# TheSmartTenDollarJob.net
KiCad netlist of a schematic drawn in EAGLE
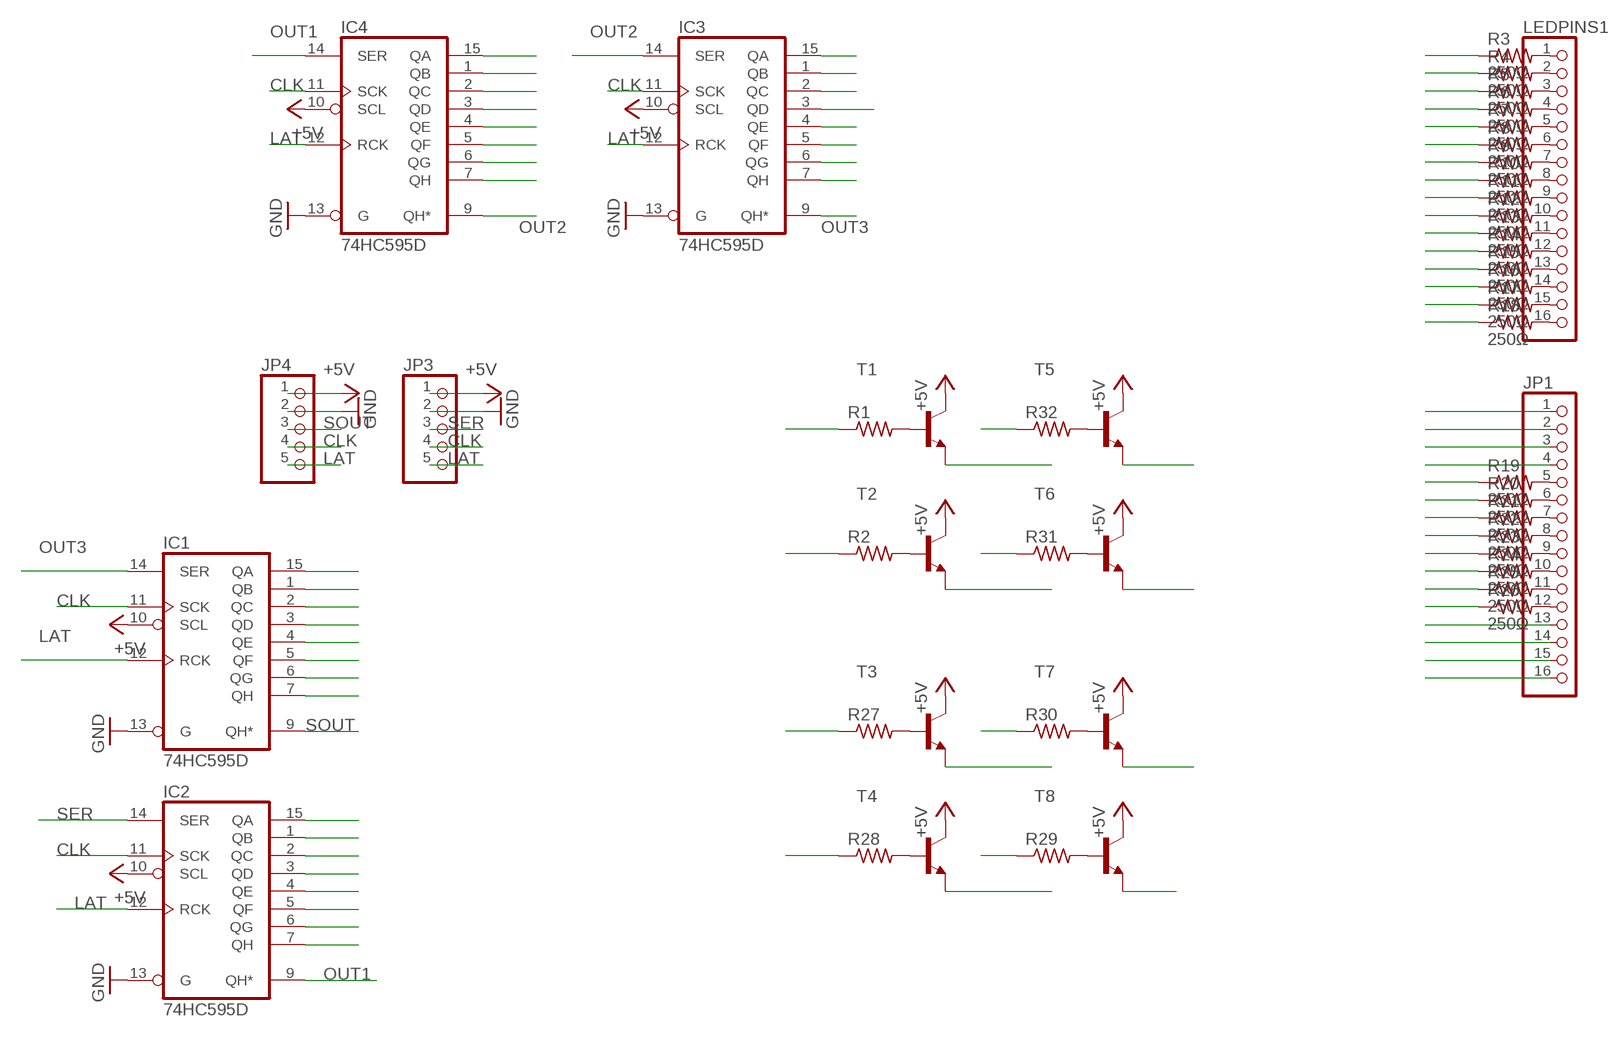
[diagram p0: schematic, sheet 1]

(export (version "E")
  (design (tool "Eeschema 10.0.6"))
  (components
    (comp (ref "IC1")
      (value "74HC595D")
      (footprint "eagle-import:SO16")
      (libsource (lib "eagle-import") (part "74595DHC"))
    )
    (comp (ref "IC2")
      (value "74HC595D")
      (footprint "eagle-import:SO16")
      (libsource (lib "eagle-import") (part "74595DHC"))
    )
    (comp (ref "IC3")
      (value "74HC595D")
      (footprint "eagle-import:SO16")
      (libsource (lib "eagle-import") (part "74595DHC"))
    )
    (comp (ref "IC4")
      (value "74HC595D")
      (footprint "eagle-import:SO16")
      (libsource (lib "eagle-import") (part "74595DHC"))
    )
    (comp (ref "JP1")
      (value "PINHD-1X16")
      (footprint "eagle-import:1X16")
      (libsource (lib "eagle-import") (part "PINHD-1X16"))
    )
    (comp (ref "JP3")
      (value "PINHD-1X5")
      (footprint "eagle-import:1X05")
      (libsource (lib "eagle-import") (part "PINHD-1X5"))
    )
    (comp (ref "JP4")
      (value "PINHD-1X5")
      (footprint "eagle-import:1X05")
      (libsource (lib "eagle-import") (part "PINHD-1X5"))
    )
    (comp (ref "LEDPINS1")
      (value "PINHD-1X16")
      (footprint "eagle-import:1X16")
      (libsource (lib "eagle-import") (part "PINHD-1X16"))
    )
    (comp (ref "R1")
      (value "R-US_R0603")
      (footprint "eagle-import:R0603")
      (libsource (lib "eagle-import") (part "resistor_R-US_R0603"))
    )
    (comp (ref "R2")
      (value "R-US_R0603")
      (footprint "eagle-import:R0603")
      (libsource (lib "eagle-import") (part "resistor_R-US_R0603"))
    )
    (comp (ref "R3")
      (value "250Ω")
      (footprint "eagle-import:R0603")
      (libsource (lib "eagle-import") (part "R-US_R0603"))
    )
    (comp (ref "R4")
      (value "250Ω")
      (footprint "eagle-import:R0603")
      (libsource (lib "eagle-import") (part "R-US_R0603"))
    )
    (comp (ref "R5")
      (value "250Ω")
      (footprint "eagle-import:R0603")
      (libsource (lib "eagle-import") (part "R-US_R0603"))
    )
    (comp (ref "R6")
      (value "250Ω")
      (footprint "eagle-import:R0603")
      (libsource (lib "eagle-import") (part "R-US_R0603"))
    )
    (comp (ref "R7")
      (value "250Ω")
      (footprint "eagle-import:R0603")
      (libsource (lib "eagle-import") (part "R-US_R0603"))
    )
    (comp (ref "R8")
      (value "250Ω")
      (footprint "eagle-import:R0603")
      (libsource (lib "eagle-import") (part "R-US_R0603"))
    )
    (comp (ref "R9")
      (value "250Ω")
      (footprint "eagle-import:R0603")
      (libsource (lib "eagle-import") (part "R-US_R0603"))
    )
    (comp (ref "R10")
      (value "250Ω")
      (footprint "eagle-import:R0603")
      (libsource (lib "eagle-import") (part "R-US_R0603"))
    )
    (comp (ref "R11")
      (value "250Ω")
      (footprint "eagle-import:R0603")
      (libsource (lib "eagle-import") (part "R-US_R0603"))
    )
    (comp (ref "R12")
      (value "250Ω")
      (footprint "eagle-import:R0603")
      (libsource (lib "eagle-import") (part "R-US_R0603"))
    )
    (comp (ref "R13")
      (value "250Ω")
      (footprint "eagle-import:R0603")
      (libsource (lib "eagle-import") (part "R-US_R0603"))
    )
    (comp (ref "R14")
      (value "250Ω")
      (footprint "eagle-import:R0603")
      (libsource (lib "eagle-import") (part "R-US_R0603"))
    )
    (comp (ref "R15")
      (value "250Ω")
      (footprint "eagle-import:R0603")
      (libsource (lib "eagle-import") (part "R-US_R0603"))
    )
    (comp (ref "R16")
      (value "250Ω")
      (footprint "eagle-import:R0603")
      (libsource (lib "eagle-import") (part "R-US_R0603"))
    )
    (comp (ref "R17")
      (value "250Ω")
      (footprint "eagle-import:R0603")
      (libsource (lib "eagle-import") (part "R-US_R0603"))
    )
    (comp (ref "R18")
      (value "250Ω")
      (footprint "eagle-import:R0603")
      (libsource (lib "eagle-import") (part "R-US_R0603"))
    )
    (comp (ref "R19")
      (value "250Ω")
      (footprint "eagle-import:R0603")
      (libsource (lib "eagle-import") (part "R-US_R0603"))
    )
    (comp (ref "R20")
      (value "250Ω")
      (footprint "eagle-import:R0603")
      (libsource (lib "eagle-import") (part "R-US_R0603"))
    )
    (comp (ref "R21")
      (value "250Ω")
      (footprint "eagle-import:R0603")
      (libsource (lib "eagle-import") (part "R-US_R0603"))
    )
    (comp (ref "R22")
      (value "250Ω")
      (footprint "eagle-import:R0603")
      (libsource (lib "eagle-import") (part "R-US_R0603"))
    )
    (comp (ref "R23")
      (value "250Ω")
      (footprint "eagle-import:R0603")
      (libsource (lib "eagle-import") (part "R-US_R0603"))
    )
    (comp (ref "R24")
      (value "250Ω")
      (footprint "eagle-import:R0603")
      (libsource (lib "eagle-import") (part "R-US_R0603"))
    )
    (comp (ref "R25")
      (value "250Ω")
      (footprint "eagle-import:R0603")
      (libsource (lib "eagle-import") (part "R-US_R0603"))
    )
    (comp (ref "R26")
      (value "250Ω")
      (footprint "eagle-import:R0603")
      (libsource (lib "eagle-import") (part "R-US_R0603"))
    )
    (comp (ref "R27")
      (value "R-US_R0603")
      (footprint "eagle-import:R0603")
      (libsource (lib "eagle-import") (part "resistor_R-US_R0603"))
    )
    (comp (ref "R28")
      (value "R-US_R0603")
      (footprint "eagle-import:R0603")
      (libsource (lib "eagle-import") (part "resistor_R-US_R0603"))
    )
    (comp (ref "R29")
      (value "R-US_R0603")
      (footprint "eagle-import:R0603")
      (libsource (lib "eagle-import") (part "resistor_R-US_R0603"))
    )
    (comp (ref "R30")
      (value "R-US_R0603")
      (footprint "eagle-import:R0603")
      (libsource (lib "eagle-import") (part "resistor_R-US_R0603"))
    )
    (comp (ref "R31")
      (value "R-US_R0603")
      (footprint "eagle-import:R0603")
      (libsource (lib "eagle-import") (part "resistor_R-US_R0603"))
    )
    (comp (ref "R32")
      (value "R-US_R0603")
      (footprint "eagle-import:R0603")
      (libsource (lib "eagle-import") (part "resistor_R-US_R0603"))
    )
    (comp (ref "T1")
      (value "-NPN-SOT23-EBC")
      (footprint "eagle-import:SOT23-EBC")
      (libsource (lib "eagle-import") (part "-NPN-SOT23-EBC"))
    )
    (comp (ref "T2")
      (value "-NPN-SOT23-EBC")
      (footprint "eagle-import:SOT23-EBC")
      (libsource (lib "eagle-import") (part "-NPN-SOT23-EBC"))
    )
    (comp (ref "T3")
      (value "-NPN-SOT23-EBC")
      (footprint "eagle-import:SOT23-EBC")
      (libsource (lib "eagle-import") (part "-NPN-SOT23-EBC"))
    )
    (comp (ref "T4")
      (value "-NPN-SOT23-EBC")
      (footprint "eagle-import:SOT23-EBC")
      (libsource (lib "eagle-import") (part "-NPN-SOT23-EBC"))
    )
    (comp (ref "T5")
      (value "-NPN-SOT23-EBC")
      (footprint "eagle-import:SOT23-EBC")
      (libsource (lib "eagle-import") (part "-NPN-SOT23-EBC"))
    )
    (comp (ref "T6")
      (value "-NPN-SOT23-EBC")
      (footprint "eagle-import:SOT23-EBC")
      (libsource (lib "eagle-import") (part "-NPN-SOT23-EBC"))
    )
    (comp (ref "T7")
      (value "-NPN-SOT23-EBC")
      (footprint "eagle-import:SOT23-EBC")
      (libsource (lib "eagle-import") (part "-NPN-SOT23-EBC"))
    )
    (comp (ref "T8")
      (value "-NPN-SOT23-EBC")
      (footprint "eagle-import:SOT23-EBC")
      (libsource (lib "eagle-import") (part "-NPN-SOT23-EBC"))
    )
  )
  (nets
    (net (code "1") (name "+5V") (class "Default")
      (node (ref "IC1") (pin "10") (pinfunction "SCL_10") (pintype "input"))
      (node (ref "IC2") (pin "10") (pinfunction "SCL_10") (pintype "input"))
      (node (ref "IC3") (pin "10") (pinfunction "SCL_10") (pintype "input"))
      (node (ref "IC4") (pin "10") (pinfunction "SCL_10") (pintype "input"))
      (node (ref "JP3") (pin "1") (pinfunction "1_1") (pintype "passive"))
      (node (ref "JP4") (pin "1") (pinfunction "1_1") (pintype "passive"))
      (node (ref "T1") (pin "C") (pinfunction "C_C") (pintype "passive"))
      (node (ref "T2") (pin "C") (pinfunction "C_C") (pintype "passive"))
      (node (ref "T3") (pin "C") (pinfunction "C_C") (pintype "passive"))
      (node (ref "T4") (pin "C") (pinfunction "C_C") (pintype "passive"))
      (node (ref "T5") (pin "C") (pinfunction "C_C") (pintype "passive"))
      (node (ref "T6") (pin "C") (pinfunction "C_C") (pintype "passive"))
      (node (ref "T7") (pin "C") (pinfunction "C_C") (pintype "passive"))
      (node (ref "T8") (pin "C") (pinfunction "C_C") (pintype "passive"))
    )
    (net (code "2") (name "/CLK") (class "Default")
      (node (ref "IC1") (pin "11") (pinfunction "SCK_11") (pintype "input"))
      (node (ref "IC2") (pin "11") (pinfunction "SCK_11") (pintype "input"))
      (node (ref "IC3") (pin "11") (pinfunction "SCK_11") (pintype "input"))
      (node (ref "IC4") (pin "11") (pinfunction "SCK_11") (pintype "input"))
      (node (ref "JP3") (pin "4") (pinfunction "4_4") (pintype "passive"))
      (node (ref "JP4") (pin "4") (pinfunction "4_4") (pintype "passive"))
    )
    (net (code "3") (name "/LAT") (class "Default")
      (node (ref "IC1") (pin "12") (pinfunction "RCK_12") (pintype "input"))
      (node (ref "IC2") (pin "12") (pinfunction "RCK_12") (pintype "input"))
      (node (ref "IC3") (pin "12") (pinfunction "RCK_12") (pintype "input"))
      (node (ref "IC4") (pin "12") (pinfunction "RCK_12") (pintype "input"))
      (node (ref "JP3") (pin "5") (pinfunction "5_5") (pintype "passive"))
      (node (ref "JP4") (pin "5") (pinfunction "5_5") (pintype "passive"))
    )
    (net (code "4") (name "/N$1") (class "Default")
      (node (ref "IC3") (pin "7") (pinfunction "QH_7") (pintype "tri_state"))
      (node (ref "R3") (pin "1") (pinfunction "1_1") (pintype "passive"))
    )
    (net (code "5") (name "/N$2") (class "Default")
      (node (ref "IC3") (pin "6") (pinfunction "QG_6") (pintype "tri_state"))
      (node (ref "R4") (pin "1") (pinfunction "1_1") (pintype "passive"))
    )
    (net (code "6") (name "/N$3") (class "Default")
      (node (ref "IC3") (pin "5") (pinfunction "QF_5") (pintype "tri_state"))
      (node (ref "R5") (pin "1") (pinfunction "1_1") (pintype "passive"))
    )
    (net (code "7") (name "/N$4") (class "Default")
      (node (ref "IC3") (pin "4") (pinfunction "QE_4") (pintype "tri_state"))
      (node (ref "R6") (pin "1") (pinfunction "1_1") (pintype "passive"))
    )
    (net (code "8") (name "/N$5") (class "Default")
      (node (ref "IC3") (pin "3") (pinfunction "QD_3") (pintype "tri_state"))
      (node (ref "R7") (pin "1") (pinfunction "1_1") (pintype "passive"))
    )
    (net (code "9") (name "/N$6") (class "Default")
      (node (ref "IC3") (pin "2") (pinfunction "QC_2") (pintype "tri_state"))
      (node (ref "R8") (pin "1") (pinfunction "1_1") (pintype "passive"))
    )
    (net (code "10") (name "/N$7") (class "Default")
      (node (ref "IC3") (pin "1") (pinfunction "QB_1") (pintype "tri_state"))
      (node (ref "R9") (pin "1") (pinfunction "1_1") (pintype "passive"))
    )
    (net (code "11") (name "/N$8") (class "Default")
      (node (ref "IC3") (pin "15") (pinfunction "QA_15") (pintype "tri_state"))
      (node (ref "R10") (pin "1") (pinfunction "1_1") (pintype "passive"))
    )
    (net (code "12") (name "/N$9") (class "Default")
      (node (ref "IC4") (pin "7") (pinfunction "QH_7") (pintype "tri_state"))
      (node (ref "R11") (pin "1") (pinfunction "1_1") (pintype "passive"))
    )
    (net (code "13") (name "/N$10") (class "Default")
      (node (ref "IC4") (pin "6") (pinfunction "QG_6") (pintype "tri_state"))
      (node (ref "R12") (pin "1") (pinfunction "1_1") (pintype "passive"))
    )
    (net (code "14") (name "/N$11") (class "Default")
      (node (ref "IC4") (pin "5") (pinfunction "QF_5") (pintype "tri_state"))
      (node (ref "R13") (pin "1") (pinfunction "1_1") (pintype "passive"))
    )
    (net (code "15") (name "/N$12") (class "Default")
      (node (ref "IC4") (pin "4") (pinfunction "QE_4") (pintype "tri_state"))
      (node (ref "R14") (pin "1") (pinfunction "1_1") (pintype "passive"))
    )
    (net (code "16") (name "/N$13") (class "Default")
      (node (ref "IC4") (pin "3") (pinfunction "QD_3") (pintype "tri_state"))
      (node (ref "R15") (pin "1") (pinfunction "1_1") (pintype "passive"))
    )
    (net (code "17") (name "/N$14") (class "Default")
      (node (ref "IC4") (pin "2") (pinfunction "QC_2") (pintype "tri_state"))
      (node (ref "R16") (pin "1") (pinfunction "1_1") (pintype "passive"))
    )
    (net (code "18") (name "/N$15") (class "Default")
      (node (ref "IC4") (pin "1") (pinfunction "QB_1") (pintype "tri_state"))
      (node (ref "R17") (pin "1") (pinfunction "1_1") (pintype "passive"))
    )
    (net (code "19") (name "/N$16") (class "Default")
      (node (ref "IC4") (pin "15") (pinfunction "QA_15") (pintype "tri_state"))
      (node (ref "R18") (pin "1") (pinfunction "1_1") (pintype "passive"))
    )
    (net (code "20") (name "/N$17") (class "Default")
      (node (ref "JP1") (pin "1") (pinfunction "1_1") (pintype "passive"))
      (node (ref "T1") (pin "E") (pinfunction "E_E") (pintype "passive"))
    )
    (net (code "21") (name "/N$18") (class "Default")
      (node (ref "JP1") (pin "2") (pinfunction "2_2") (pintype "passive"))
      (node (ref "T2") (pin "E") (pinfunction "E_E") (pintype "passive"))
    )
    (net (code "22") (name "/N$19") (class "Default")
      (node (ref "JP1") (pin "3") (pinfunction "3_3") (pintype "passive"))
      (node (ref "T3") (pin "E") (pinfunction "E_E") (pintype "passive"))
    )
    (net (code "23") (name "/N$20") (class "Default")
      (node (ref "JP1") (pin "4") (pinfunction "4_4") (pintype "passive"))
      (node (ref "T4") (pin "E") (pinfunction "E_E") (pintype "passive"))
    )
    (net (code "24") (name "/N$21") (class "Default")
      (node (ref "IC1") (pin "4") (pinfunction "QE_4") (pintype "tri_state"))
      (node (ref "R19") (pin "1") (pinfunction "1_1") (pintype "passive"))
    )
    (net (code "25") (name "/N$22") (class "Default")
      (node (ref "IC1") (pin "5") (pinfunction "QF_5") (pintype "tri_state"))
      (node (ref "R20") (pin "1") (pinfunction "1_1") (pintype "passive"))
    )
    (net (code "26") (name "/N$23") (class "Default")
      (node (ref "IC1") (pin "6") (pinfunction "QG_6") (pintype "tri_state"))
      (node (ref "R21") (pin "1") (pinfunction "1_1") (pintype "passive"))
    )
    (net (code "27") (name "/N$24") (class "Default")
      (node (ref "IC1") (pin "7") (pinfunction "QH_7") (pintype "tri_state"))
      (node (ref "R22") (pin "1") (pinfunction "1_1") (pintype "passive"))
    )
    (net (code "28") (name "/N$25") (class "Default")
      (node (ref "IC2") (pin "15") (pinfunction "QA_15") (pintype "tri_state"))
      (node (ref "R23") (pin "1") (pinfunction "1_1") (pintype "passive"))
    )
    (net (code "29") (name "/N$26") (class "Default")
      (node (ref "IC2") (pin "1") (pinfunction "QB_1") (pintype "tri_state"))
      (node (ref "R24") (pin "1") (pinfunction "1_1") (pintype "passive"))
    )
    (net (code "30") (name "/N$27") (class "Default")
      (node (ref "IC2") (pin "2") (pinfunction "QC_2") (pintype "tri_state"))
      (node (ref "R25") (pin "1") (pinfunction "1_1") (pintype "passive"))
    )
    (net (code "31") (name "/N$28") (class "Default")
      (node (ref "IC2") (pin "3") (pinfunction "QD_3") (pintype "tri_state"))
      (node (ref "R26") (pin "1") (pinfunction "1_1") (pintype "passive"))
    )
    (net (code "32") (name "/N$29") (class "Default")
      (node (ref "JP1") (pin "13") (pinfunction "13_13") (pintype "passive"))
      (node (ref "T5") (pin "E") (pinfunction "E_E") (pintype "passive"))
    )
    (net (code "33") (name "/N$30") (class "Default")
      (node (ref "JP1") (pin "14") (pinfunction "14_14") (pintype "passive"))
      (node (ref "T6") (pin "E") (pinfunction "E_E") (pintype "passive"))
    )
    (net (code "34") (name "/N$31") (class "Default")
      (node (ref "JP1") (pin "15") (pinfunction "15_15") (pintype "passive"))
      (node (ref "T7") (pin "E") (pinfunction "E_E") (pintype "passive"))
    )
    (net (code "35") (name "/N$32") (class "Default")
      (node (ref "JP1") (pin "16") (pinfunction "16_16") (pintype "passive"))
      (node (ref "T8") (pin "E") (pinfunction "E_E") (pintype "passive"))
    )
    (net (code "36") (name "/OUT1") (class "Default")
      (node (ref "IC2") (pin "9") (pinfunction "QH*_9") (pintype "tri_state"))
      (node (ref "IC4") (pin "14") (pinfunction "SER_14") (pintype "input"))
    )
    (net (code "37") (name "/OUT2") (class "Default")
      (node (ref "IC3") (pin "14") (pinfunction "SER_14") (pintype "input"))
      (node (ref "IC4") (pin "9") (pinfunction "QH*_9") (pintype "tri_state"))
    )
    (net (code "38") (name "/OUT3") (class "Default")
      (node (ref "IC1") (pin "14") (pinfunction "SER_14") (pintype "input"))
      (node (ref "IC3") (pin "9") (pinfunction "QH*_9") (pintype "tri_state"))
    )
    (net (code "39") (name "/QA") (class "Default")
      (node (ref "IC1") (pin "15") (pinfunction "QA_15") (pintype "tri_state"))
      (node (ref "R1") (pin "1") (pinfunction "1_1") (pintype "passive"))
    )
    (net (code "40") (name "/QB") (class "Default")
      (node (ref "IC1") (pin "1") (pinfunction "QB_1") (pintype "tri_state"))
      (node (ref "R2") (pin "1") (pinfunction "1_1") (pintype "passive"))
    )
    (net (code "41") (name "/QC") (class "Default")
      (node (ref "IC1") (pin "2") (pinfunction "QC_2") (pintype "tri_state"))
      (node (ref "R27") (pin "1") (pinfunction "1_1") (pintype "passive"))
    )
    (net (code "42") (name "/QD") (class "Default")
      (node (ref "IC1") (pin "3") (pinfunction "QD_3") (pintype "tri_state"))
      (node (ref "R28") (pin "1") (pinfunction "1_1") (pintype "passive"))
    )
    (net (code "43") (name "/QE") (class "Default")
      (node (ref "IC2") (pin "4") (pinfunction "QE_4") (pintype "tri_state"))
      (node (ref "R32") (pin "1") (pinfunction "1_1") (pintype "passive"))
    )
    (net (code "44") (name "/QF") (class "Default")
      (node (ref "IC2") (pin "5") (pinfunction "QF_5") (pintype "tri_state"))
      (node (ref "R31") (pin "1") (pinfunction "1_1") (pintype "passive"))
    )
    (net (code "45") (name "/QG") (class "Default")
      (node (ref "IC2") (pin "6") (pinfunction "QG_6") (pintype "tri_state"))
      (node (ref "R30") (pin "1") (pinfunction "1_1") (pintype "passive"))
    )
    (net (code "46") (name "/QH") (class "Default")
      (node (ref "IC2") (pin "7") (pinfunction "QH_7") (pintype "tri_state"))
      (node (ref "R29") (pin "1") (pinfunction "1_1") (pintype "passive"))
    )
    (net (code "47") (name "/SER") (class "Default")
      (node (ref "IC2") (pin "14") (pinfunction "SER_14") (pintype "input"))
      (node (ref "JP3") (pin "3") (pinfunction "3_3") (pintype "passive"))
    )
    (net (code "48") (name "/SOUT") (class "Default")
      (node (ref "IC1") (pin "9") (pinfunction "QH*_9") (pintype "tri_state"))
      (node (ref "JP4") (pin "3") (pinfunction "3_3") (pintype "passive"))
    )
    (net (code "49") (name "GND") (class "Default")
      (node (ref "IC1") (pin "13") (pinfunction "G_13") (pintype "input"))
      (node (ref "IC2") (pin "13") (pinfunction "G_13") (pintype "input"))
      (node (ref "IC3") (pin "13") (pinfunction "G_13") (pintype "input"))
      (node (ref "IC4") (pin "13") (pinfunction "G_13") (pintype "input"))
      (node (ref "JP3") (pin "2") (pinfunction "2_2") (pintype "passive"))
      (node (ref "JP4") (pin "2") (pinfunction "2_2") (pintype "passive"))
    )
    (net (code "50") (name "Net-(JP1-Pad5)") (class "Default")
      (node (ref "JP1") (pin "5") (pinfunction "5_5") (pintype "passive"))
      (node (ref "R19") (pin "2") (pinfunction "2_2") (pintype "passive"))
    )
    (net (code "51") (name "Net-(JP1-Pad6)") (class "Default")
      (node (ref "JP1") (pin "6") (pinfunction "6_6") (pintype "passive"))
      (node (ref "R20") (pin "2") (pinfunction "2_2") (pintype "passive"))
    )
    (net (code "52") (name "Net-(JP1-Pad7)") (class "Default")
      (node (ref "JP1") (pin "7") (pinfunction "7_7") (pintype "passive"))
      (node (ref "R21") (pin "2") (pinfunction "2_2") (pintype "passive"))
    )
    (net (code "53") (name "Net-(JP1-Pad8)") (class "Default")
      (node (ref "JP1") (pin "8") (pinfunction "8_8") (pintype "passive"))
      (node (ref "R22") (pin "2") (pinfunction "2_2") (pintype "passive"))
    )
    (net (code "54") (name "Net-(JP1-Pad9)") (class "Default")
      (node (ref "JP1") (pin "9") (pinfunction "9_9") (pintype "passive"))
      (node (ref "R23") (pin "2") (pinfunction "2_2") (pintype "passive"))
    )
    (net (code "55") (name "Net-(JP1-Pad10)") (class "Default")
      (node (ref "JP1") (pin "10") (pinfunction "10_10") (pintype "passive"))
      (node (ref "R24") (pin "2") (pinfunction "2_2") (pintype "passive"))
    )
    (net (code "56") (name "Net-(JP1-Pad11)") (class "Default")
      (node (ref "JP1") (pin "11") (pinfunction "11_11") (pintype "passive"))
      (node (ref "R25") (pin "2") (pinfunction "2_2") (pintype "passive"))
    )
    (net (code "57") (name "Net-(JP1-Pad12)") (class "Default")
      (node (ref "JP1") (pin "12") (pinfunction "12_12") (pintype "passive"))
      (node (ref "R26") (pin "2") (pinfunction "2_2") (pintype "passive"))
    )
    (net (code "58") (name "Net-(LEDPINS1-Pad1)") (class "Default")
      (node (ref "LEDPINS1") (pin "1") (pinfunction "1_1") (pintype "passive"))
      (node (ref "R3") (pin "2") (pinfunction "2_2") (pintype "passive"))
    )
    (net (code "59") (name "Net-(LEDPINS1-Pad2)") (class "Default")
      (node (ref "LEDPINS1") (pin "2") (pinfunction "2_2") (pintype "passive"))
      (node (ref "R4") (pin "2") (pinfunction "2_2") (pintype "passive"))
    )
    (net (code "60") (name "Net-(LEDPINS1-Pad3)") (class "Default")
      (node (ref "LEDPINS1") (pin "3") (pinfunction "3_3") (pintype "passive"))
      (node (ref "R5") (pin "2") (pinfunction "2_2") (pintype "passive"))
    )
    (net (code "61") (name "Net-(LEDPINS1-Pad4)") (class "Default")
      (node (ref "LEDPINS1") (pin "4") (pinfunction "4_4") (pintype "passive"))
      (node (ref "R6") (pin "2") (pinfunction "2_2") (pintype "passive"))
    )
    (net (code "62") (name "Net-(LEDPINS1-Pad5)") (class "Default")
      (node (ref "LEDPINS1") (pin "5") (pinfunction "5_5") (pintype "passive"))
      (node (ref "R7") (pin "2") (pinfunction "2_2") (pintype "passive"))
    )
    (net (code "63") (name "Net-(LEDPINS1-Pad6)") (class "Default")
      (node (ref "LEDPINS1") (pin "6") (pinfunction "6_6") (pintype "passive"))
      (node (ref "R8") (pin "2") (pinfunction "2_2") (pintype "passive"))
    )
    (net (code "64") (name "Net-(LEDPINS1-Pad7)") (class "Default")
      (node (ref "LEDPINS1") (pin "7") (pinfunction "7_7") (pintype "passive"))
      (node (ref "R9") (pin "2") (pinfunction "2_2") (pintype "passive"))
    )
    (net (code "65") (name "Net-(LEDPINS1-Pad8)") (class "Default")
      (node (ref "LEDPINS1") (pin "8") (pinfunction "8_8") (pintype "passive"))
      (node (ref "R10") (pin "2") (pinfunction "2_2") (pintype "passive"))
    )
    (net (code "66") (name "Net-(LEDPINS1-Pad9)") (class "Default")
      (node (ref "LEDPINS1") (pin "9") (pinfunction "9_9") (pintype "passive"))
      (node (ref "R11") (pin "2") (pinfunction "2_2") (pintype "passive"))
    )
    (net (code "67") (name "Net-(LEDPINS1-Pad10)") (class "Default")
      (node (ref "LEDPINS1") (pin "10") (pinfunction "10_10") (pintype "passive"))
      (node (ref "R12") (pin "2") (pinfunction "2_2") (pintype "passive"))
    )
    (net (code "68") (name "Net-(LEDPINS1-Pad11)") (class "Default")
      (node (ref "LEDPINS1") (pin "11") (pinfunction "11_11") (pintype "passive"))
      (node (ref "R13") (pin "2") (pinfunction "2_2") (pintype "passive"))
    )
    (net (code "69") (name "Net-(LEDPINS1-Pad12)") (class "Default")
      (node (ref "LEDPINS1") (pin "12") (pinfunction "12_12") (pintype "passive"))
      (node (ref "R14") (pin "2") (pinfunction "2_2") (pintype "passive"))
    )
    (net (code "70") (name "Net-(LEDPINS1-Pad13)") (class "Default")
      (node (ref "LEDPINS1") (pin "13") (pinfunction "13_13") (pintype "passive"))
      (node (ref "R15") (pin "2") (pinfunction "2_2") (pintype "passive"))
    )
    (net (code "71") (name "Net-(LEDPINS1-Pad14)") (class "Default")
      (node (ref "LEDPINS1") (pin "14") (pinfunction "14_14") (pintype "passive"))
      (node (ref "R16") (pin "2") (pinfunction "2_2") (pintype "passive"))
    )
    (net (code "72") (name "Net-(LEDPINS1-Pad15)") (class "Default")
      (node (ref "LEDPINS1") (pin "15") (pinfunction "15_15") (pintype "passive"))
      (node (ref "R17") (pin "2") (pinfunction "2_2") (pintype "passive"))
    )
    (net (code "73") (name "Net-(LEDPINS1-Pad16)") (class "Default")
      (node (ref "LEDPINS1") (pin "16") (pinfunction "16_16") (pintype "passive"))
      (node (ref "R18") (pin "2") (pinfunction "2_2") (pintype "passive"))
    )
    (net (code "74") (name "Net-(R1-Pad2)") (class "Default")
      (node (ref "R1") (pin "2") (pinfunction "2_2") (pintype "passive"))
      (node (ref "T1") (pin "B") (pinfunction "B_B") (pintype "passive"))
    )
    (net (code "75") (name "Net-(R2-Pad2)") (class "Default")
      (node (ref "R2") (pin "2") (pinfunction "2_2") (pintype "passive"))
      (node (ref "T2") (pin "B") (pinfunction "B_B") (pintype "passive"))
    )
    (net (code "76") (name "Net-(R27-Pad2)") (class "Default")
      (node (ref "R27") (pin "2") (pinfunction "2_2") (pintype "passive"))
      (node (ref "T3") (pin "B") (pinfunction "B_B") (pintype "passive"))
    )
    (net (code "77") (name "Net-(R28-Pad2)") (class "Default")
      (node (ref "R28") (pin "2") (pinfunction "2_2") (pintype "passive"))
      (node (ref "T4") (pin "B") (pinfunction "B_B") (pintype "passive"))
    )
    (net (code "78") (name "Net-(R29-Pad2)") (class "Default")
      (node (ref "R29") (pin "2") (pinfunction "2_2") (pintype "passive"))
      (node (ref "T8") (pin "B") (pinfunction "B_B") (pintype "passive"))
    )
    (net (code "79") (name "Net-(R30-Pad2)") (class "Default")
      (node (ref "R30") (pin "2") (pinfunction "2_2") (pintype "passive"))
      (node (ref "T7") (pin "B") (pinfunction "B_B") (pintype "passive"))
    )
    (net (code "80") (name "Net-(R31-Pad2)") (class "Default")
      (node (ref "R31") (pin "2") (pinfunction "2_2") (pintype "passive"))
      (node (ref "T6") (pin "B") (pinfunction "B_B") (pintype "passive"))
    )
    (net (code "81") (name "Net-(R32-Pad2)") (class "Default")
      (node (ref "R32") (pin "2") (pinfunction "2_2") (pintype "passive"))
      (node (ref "T5") (pin "B") (pinfunction "B_B") (pintype "passive"))
    )
  )
)
